# projet_pcb_etu_PIC18.net
KiCad netlist of a schematic drawn in Altium Designer
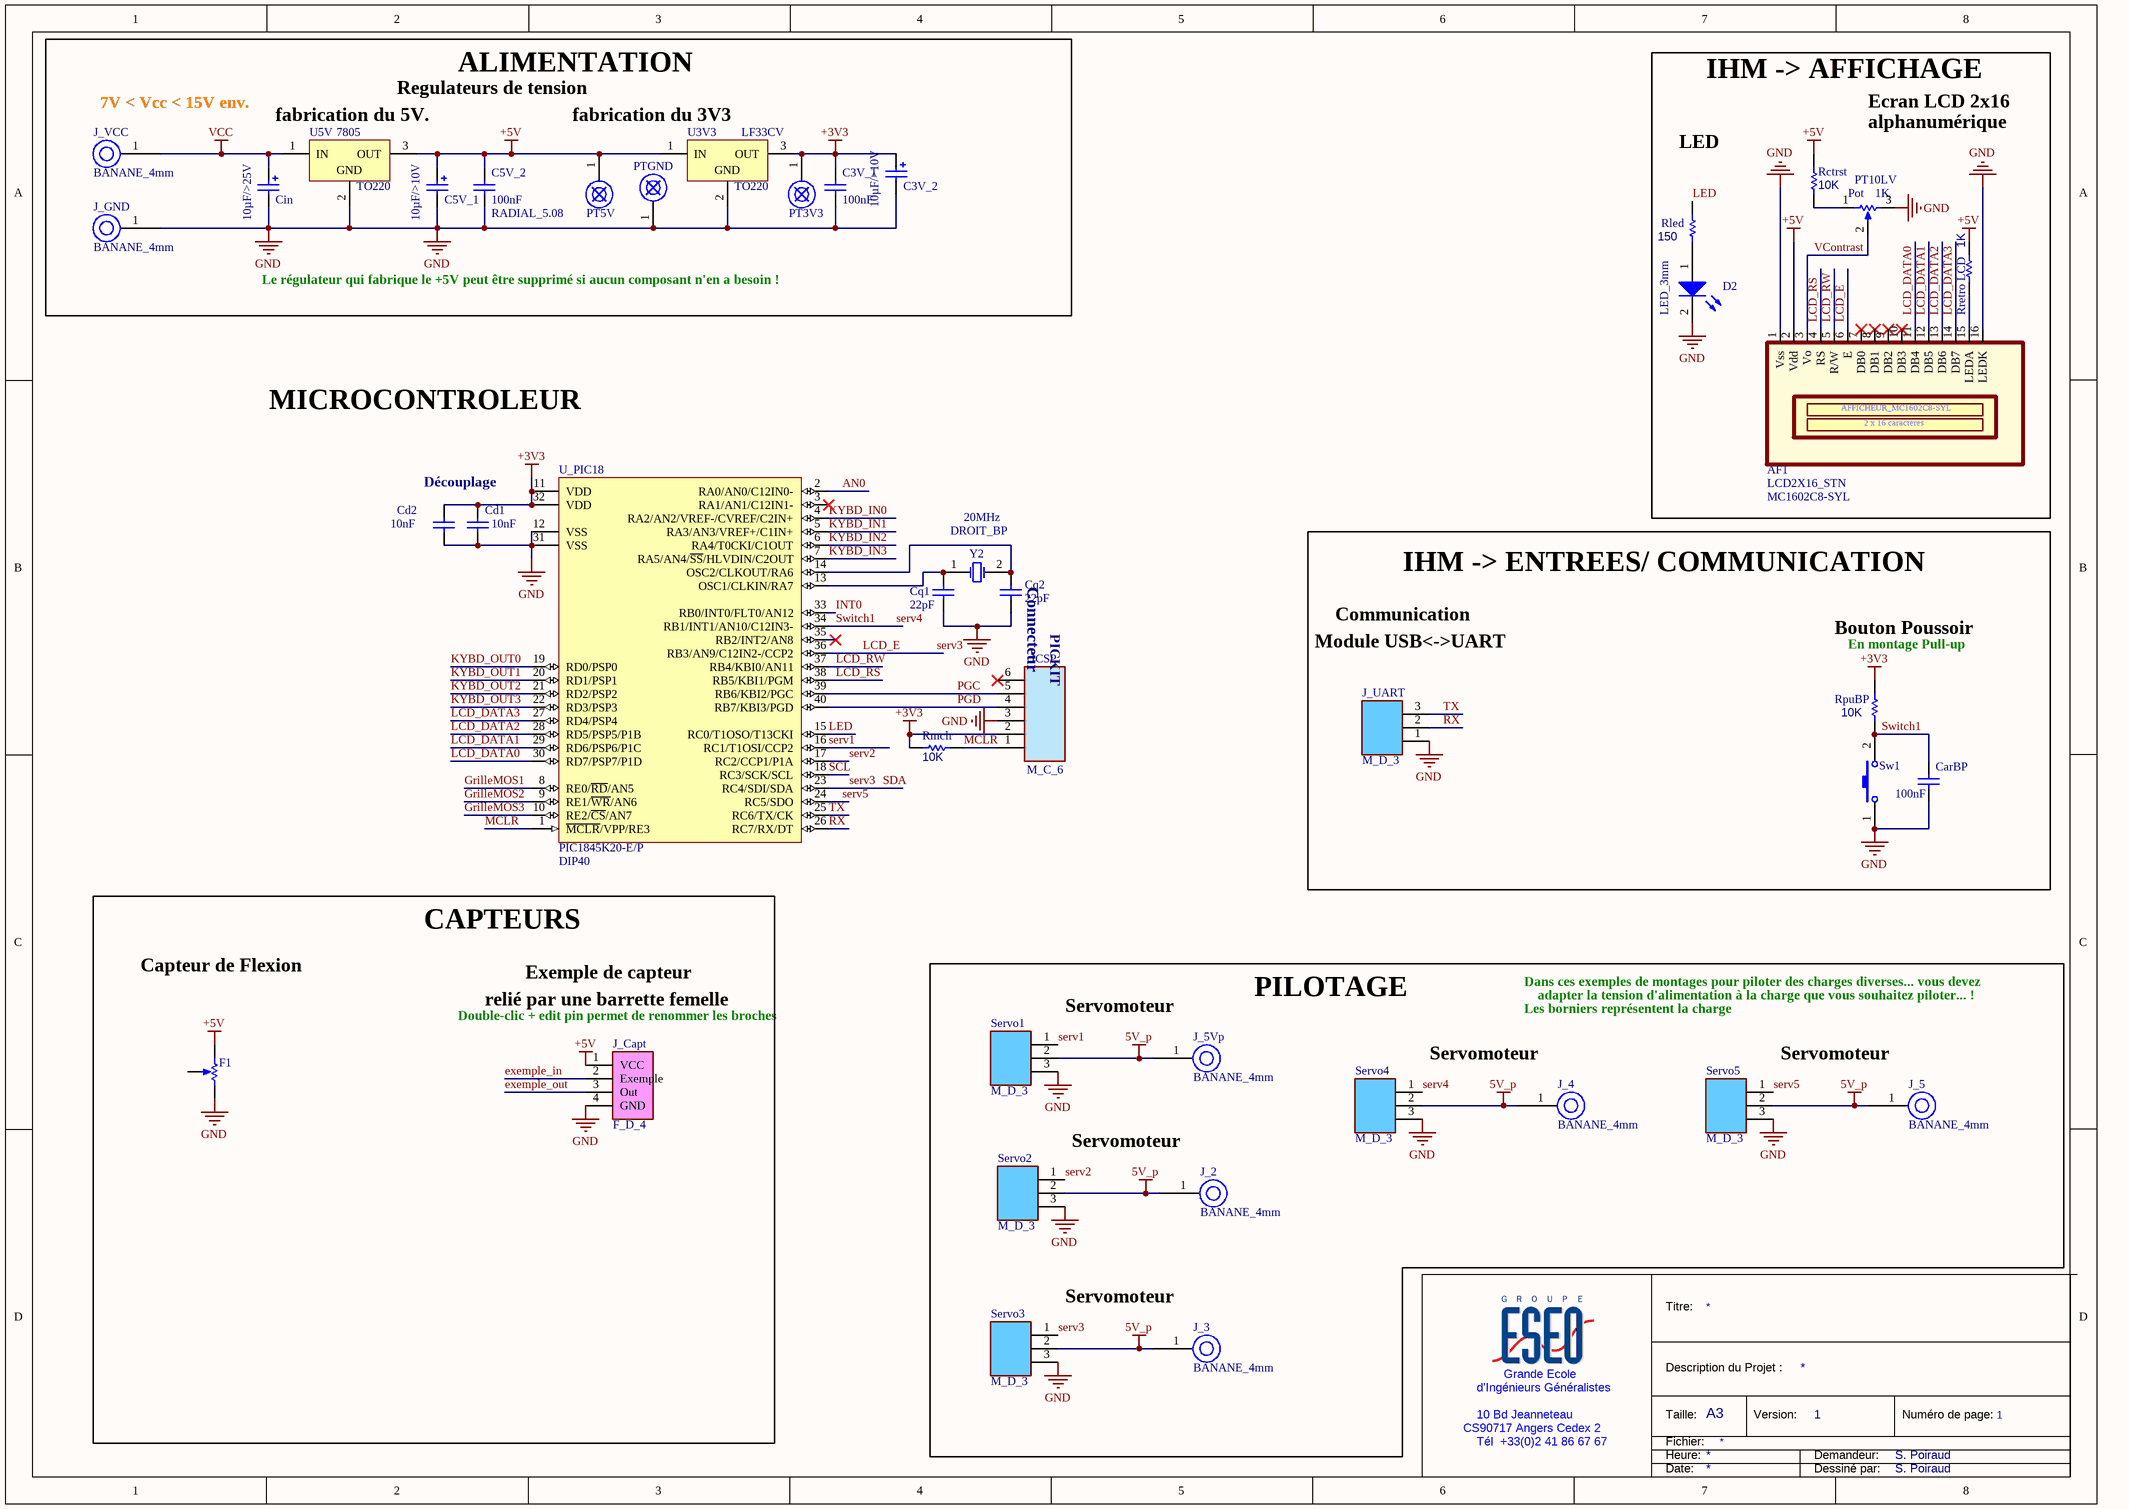
[diagram p0: projet_pcb_etu_PIC18.SchDoc]

(export (version "E")
  (design (tool "Eeschema 10.0.6"))
  (components
    (comp (ref "AF1")
      (value "AFFICHEUR_LCD_2X16_")
      (footprint "AFFICHEUR_LCD_MC1602C8-SYL")
      (description "AFFICHEUR LCD - 2x16 LIGNES - 5X7 DOTS - STN - 80mm x 36mm")
      (fields (field (name "TYPE") "LCD2X16_STN") (field (name "NAME") "MC1602C8-SYL"))
      (libsource (lib "affichage") (part "AFFICHEUR_LCD_MC1602C8-SYL"))
    )
    (comp (ref "C3V_1")
      (value "100nF")
      (footprint "CONDENSATEUR_CERAMIQUE_RADIAL_5.08")
      (description "CONDENSATEUR TRAVERSANT CERAMIQUE RADIAL 5.08mm")
      (fields (field (name "Comment") "CONDENSATEUR_CER_RAD_5.08"))
      (libsource (lib "composants passifs") (part "CONDENSATEUR_CER_RAD_5.08"))
    )
    (comp (ref "C3V_2")
      (value "10µF/>10V")
      (footprint "CONDENSATEUR_POLARISE_ELECTROLYTIQUE_RADIAL_2.0/5.08")
      (description "CONDENSATEUR POLARISE ELECTROLYTIQUE RADIAL 2.0/5.08")
      (fields (field (name "Comment") "CONDENSATEUR_POL_ELECTROLY_RAD_2.0/5.08"))
      (libsource (lib "composants passifs") (part "CONDENSATEUR_POL_ELECTROLY_RAD_2.0/5.08"))
    )
    (comp (ref "C5V_1")
      (value "10µF/>10V")
      (footprint "CONDENSATEUR_POLARISE_ELECTROLYTIQUE_RADIAL_2.0/5.08")
      (description "CONDENSATEUR POLARISE ELECTROLYTIQUE RADIAL 2.0/5.08")
      (fields (field (name "Comment") "CONDENSATEUR_POL_ELECTROLY_RAD_2.0/5.08"))
      (libsource (lib "composants passifs") (part "CONDENSATEUR_POL_ELECTROLY_RAD_2.0/5.08"))
    )
    (comp (ref "C5V_2")
      (value "100nF")
      (footprint "CONDENSATEUR_CERAMIQUE_RADIAL_5.08")
      (description "CONDENSATEUR TRAVERSANT CERAMIQUE RADIAL 5.08mm")
      (fields (field (name "TYPE") "RADIAL_5.08") (field (name "Comment") "CONDENSATEUR_CER_RAD_5.08"))
      (libsource (lib "composants passifs") (part "CONDENSATEUR_CER_RAD_5.08"))
    )
    (comp (ref "CarBP")
      (value "100nF")
      (footprint "CONDENSATEUR_CERAMIQUE_RADIAL_5.08")
      (description "CONDENSATEUR TRAVERSANT CERAMIQUE RADIAL 5.08mm")
      (fields (field (name "Comment") "CONDENSATEUR_CER_RAD_5.08"))
      (libsource (lib "composants passifs") (part "CONDENSATEUR_CER_RAD_5.08"))
    )
    (comp (ref "Cd1")
      (value "10nF")
      (footprint "CONDENSATEUR_CERAMIQUE_RADIAL_5.08")
      (description "CONDENSATEUR TRAVERSANT CERAMIQUE RADIAL 5.08mm")
      (fields (field (name "Comment") "CONDENSATEUR_CER_RAD_5.08"))
      (libsource (lib "composants passifs") (part "CONDENSATEUR_CER_RAD_5.08"))
    )
    (comp (ref "Cd2")
      (value "10nF")
      (footprint "CONDENSATEUR_CERAMIQUE_RADIAL_5.08")
      (description "CONDENSATEUR TRAVERSANT CERAMIQUE RADIAL 5.08mm")
      (fields (field (name "Comment") "CONDENSATEUR_CER_RAD_5.08"))
      (libsource (lib "composants passifs") (part "CONDENSATEUR_CER_RAD_5.08"))
    )
    (comp (ref "Cin")
      (value "10µF/>25V")
      (footprint "CONDENSATEUR_POLARISE_ELECTROLYTIQUE_RADIAL_2.0/5.08")
      (description "CONDENSATEUR POLARISE ELECTROLYTIQUE RADIAL 2.0/5.08")
      (fields (field (name "Comment") "CONDENSATEUR_POL_ELECTROLY_RAD_2.0/5.08"))
      (libsource (lib "composants passifs") (part "CONDENSATEUR_POL_ELECTROLY_RAD_2.0/5.08"))
    )
    (comp (ref "Cq1")
      (value "22pF")
      (footprint "CONDENSATEUR_CERAMIQUE_RADIAL_5.08")
      (description "CONDENSATEUR TRAVERSANT CERAMIQUE RADIAL 5.08mm")
      (fields (field (name "Comment") "CONDENSATEUR_CER_RAD_5.08"))
      (libsource (lib "composants passifs") (part "CONDENSATEUR_CER_RAD_5.08"))
    )
    (comp (ref "Cq2")
      (value "22pF")
      (footprint "CONDENSATEUR_CERAMIQUE_RADIAL_5.08")
      (description "CONDENSATEUR TRAVERSANT CERAMIQUE RADIAL 5.08mm")
      (fields (field (name "Comment") "CONDENSATEUR_CER_RAD_5.08"))
      (libsource (lib "composants passifs") (part "CONDENSATEUR_CER_RAD_5.08"))
    )
    (comp (ref "D2")
      (value "LED_3MM")
      (footprint "LED_3MM")
      (description "LED 3MM - ROUGE/VERTE/JAUNE")
      (fields (field (name "TYPE") "LED_3mm"))
      (libsource (lib "affichage") (part "LED_3MM"))
    )
    (comp (ref "F1")
      (value "Potentiometer")
      (libsource (lib "Simulation Generic Components") (part "Potentiometer"))
    )
    (comp (ref "ICSP")
      (value "BARRETTE_6 CONTACTS_1 RANGEE_MALE_COUDEE")
      (footprint "BARRETTE_6_M_C")
      (description "BARRETTE 6 CONTACTS 1 RANGEE MALE COUDEE")
      (fields (field (name "TYPE") "M_C_6"))
      (libsource (lib "connecteurs") (part "BARRETTE_6 CONTACTS_1 RANGEE_MALE_COUDEE"))
    )
    (comp (ref "J_2")
      (value "DOUILLE BANANE 4mm")
      (footprint "DOUILLE_BANANE_4mm")
      (description "DOUILLE BANANE 4 mm")
      (fields (field (name "TYPE") "BANANE_4mm"))
      (libsource (lib "connecteurs") (part "DOUILLE_BANANE_4mm"))
    )
    (comp (ref "J_3")
      (value "DOUILLE BANANE 4mm")
      (footprint "DOUILLE_BANANE_4mm")
      (description "DOUILLE BANANE 4 mm")
      (fields (field (name "TYPE") "BANANE_4mm"))
      (libsource (lib "connecteurs") (part "DOUILLE_BANANE_4mm"))
    )
    (comp (ref "J_4")
      (value "DOUILLE BANANE 4mm")
      (footprint "DOUILLE_BANANE_4mm")
      (description "DOUILLE BANANE 4 mm")
      (fields (field (name "TYPE") "BANANE_4mm"))
      (libsource (lib "connecteurs") (part "DOUILLE_BANANE_4mm"))
    )
    (comp (ref "J_5")
      (value "DOUILLE BANANE 4mm")
      (footprint "DOUILLE_BANANE_4mm")
      (description "DOUILLE BANANE 4 mm")
      (fields (field (name "TYPE") "BANANE_4mm"))
      (libsource (lib "connecteurs") (part "DOUILLE_BANANE_4mm"))
    )
    (comp (ref "J_5Vp")
      (value "DOUILLE BANANE 4mm")
      (footprint "DOUILLE_BANANE_4mm")
      (description "DOUILLE BANANE 4 mm")
      (fields (field (name "TYPE") "BANANE_4mm"))
      (libsource (lib "connecteurs") (part "DOUILLE_BANANE_4mm"))
    )
    (comp (ref "J_Capt")
      (value "BARRETTE_4 CONTACTS_1 RANGEE_FEMELLE_DROITE")
      (footprint "BARRETTE_4_F_D")
      (description "BARRETTE 4 CONTACTS 1 RANGEE FEMELLE DROITE")
      (fields (field (name "TYPE") "F_D_4"))
      (libsource (lib "connecteurs") (part "BARRETTE_4 CONTACTS_1 RANGEE_FEMELLE_DROITE"))
    )
    (comp (ref "J_GND")
      (value "DOUILLE BANANE 4mm")
      (footprint "DOUILLE_BANANE_4mm")
      (description "DOUILLE BANANE 4 mm")
      (fields (field (name "TYPE") "BANANE_4mm"))
      (libsource (lib "connecteurs") (part "DOUILLE_BANANE_4mm"))
    )
    (comp (ref "J_UART")
      (value "BARRETTE 3 CONTACTS 1 RANGEE MALE DROITE")
      (footprint "BARRETTE_3_M_D")
      (fields (field (name "TYPE") "M_D_3"))
      (libsource (lib "") (part "BARRETTE_3 CONTACTS_1 RANGEE_MALE_DROITE_1"))
    )
    (comp (ref "J_VCC")
      (value "DOUILLE BANANE 4mm")
      (footprint "DOUILLE_BANANE_4mm")
      (description "DOUILLE BANANE 4 mm")
      (fields (field (name "TYPE") "BANANE_4mm"))
      (libsource (lib "connecteurs") (part "DOUILLE_BANANE_4mm"))
    )
    (comp (ref "Pot")
      (value "1K")
      (footprint "TRIMMER_MONOTOUR_PT10LV")
      (description "RESISTANCE VARIABLE_TRAVERSANTE : PT10LV")
      (fields
        (field (name "TYPE") "PT10LV")
        (field (name "Comment") "RESISTANCE_VARIABLE_TRAVERSANTE : PT10LV")
      )
      (libsource (lib "composants passifs") (part "RESISTANCE_VARIABLE_TRAVERSANTE {colon} PT10LV"))
    )
    (comp (ref "PT3V3")
      (value "POINT_TEST")
      (footprint "POINT_TEST")
      (description "POINT TEST")
      (libsource (lib "connecteurs") (part "POINT_TEST"))
    )
    (comp (ref "PT5V")
      (value "POINT_TEST")
      (footprint "POINT_TEST")
      (description "POINT TEST")
      (libsource (lib "connecteurs") (part "POINT_TEST"))
    )
    (comp (ref "PTGND")
      (value "POINT_TEST")
      (footprint "POINT_TEST")
      (description "POINT TEST")
      (libsource (lib "connecteurs") (part "POINT_TEST"))
    )
    (comp (ref "Rctrst")
      (value "10K")
      (footprint "RESISTANCE_1/4W")
      (description "RESISTANCE TRAVERSANTE AXIALE 1/4W")
      (fields (field (name "Comment") "RESISTANCE_AXIALE_1/4W"))
      (libsource (lib "composants passifs") (part "RESISTANCE_AXIALE_1/4W"))
    )
    (comp (ref "Rled")
      (value "150")
      (footprint "RESISTANCE_1/4W")
      (description "RESISTANCE TRAVERSANTE AXIALE 1/4W")
      (fields (field (name "Comment") "RESISTANCE_AXIALE_1/4W"))
      (libsource (lib "composants passifs") (part "RESISTANCE_AXIALE_1/4W"))
    )
    (comp (ref "Rmclr")
      (value "10K")
      (footprint "RESISTANCE_1/4W")
      (description "RESISTANCE TRAVERSANTE AXIALE 1/4W")
      (fields (field (name "Comment") "RESISTANCE_AXIALE_1/4W"))
      (libsource (lib "composants passifs") (part "RESISTANCE_AXIALE_1/4W"))
    )
    (comp (ref "RpuBP")
      (value "10K")
      (footprint "RESISTANCE_1/4W")
      (description "RESISTANCE TRAVERSANTE AXIALE 1/4W")
      (fields (field (name "Comment") "RESISTANCE_AXIALE_1/4W"))
      (libsource (lib "composants passifs") (part "RESISTANCE_AXIALE_1/4W"))
    )
    (comp (ref "Rretro LCD")
      (value "1K")
      (footprint "RESISTANCE_1/4W")
      (description "RESISTANCE TRAVERSANTE AXIALE 1/4W")
      (fields (field (name "Comment") "RESISTANCE_AXIALE_1/4W"))
      (libsource (lib "composants passifs") (part "RESISTANCE_AXIALE_1/4W"))
    )
    (comp (ref "Servo1")
      (value "BARRETTE 3 CONTACTS 1 RANGEE MALE DROITE")
      (footprint "BARRETTE_3_M_D")
      (fields (field (name "TYPE") "M_D_3"))
      (libsource (lib "connecteurs") (part "BARRETTE_3 CONTACTS_1 RANGEE_MALE_DROITE"))
    )
    (comp (ref "Servo2")
      (value "BARRETTE 3 CONTACTS 1 RANGEE MALE DROITE")
      (footprint "BARRETTE_3_M_D")
      (fields (field (name "TYPE") "M_D_3"))
      (libsource (lib "connecteurs") (part "BARRETTE_3 CONTACTS_1 RANGEE_MALE_DROITE"))
    )
    (comp (ref "Servo3")
      (value "BARRETTE 3 CONTACTS 1 RANGEE MALE DROITE")
      (footprint "BARRETTE_3_M_D")
      (fields (field (name "TYPE") "M_D_3"))
      (libsource (lib "connecteurs") (part "BARRETTE_3 CONTACTS_1 RANGEE_MALE_DROITE"))
    )
    (comp (ref "Servo4")
      (value "BARRETTE 3 CONTACTS 1 RANGEE MALE DROITE")
      (footprint "BARRETTE_3_M_D")
      (fields (field (name "TYPE") "M_D_3"))
      (libsource (lib "connecteurs") (part "BARRETTE_3 CONTACTS_1 RANGEE_MALE_DROITE"))
    )
    (comp (ref "Servo5")
      (value "BARRETTE 3 CONTACTS 1 RANGEE MALE DROITE")
      (footprint "BARRETTE_3_M_D")
      (fields (field (name "TYPE") "M_D_3"))
      (libsource (lib "connecteurs") (part "BARRETTE_3 CONTACTS_1 RANGEE_MALE_DROITE"))
    )
    (comp (ref "Sw1")
      (value "BOUTON_POUSSOIR_MINIATURE_TRAVERSANT")
      (footprint "BOUTON_POUSSE_PLAT_6x6")
      (description "BOUTON POUSSOIR MINIATURE TRAVERSANT ON/OFF")
      (libsource (lib "commutation") (part "BOUTON_POUSSOIR_MINIATURE_TRAVERSANT"))
    )
    (comp (ref "U3V3")
      (value "REGULATEUR_TO220_78XX")
      (footprint "REGULATEUR_TO220_78XX")
      (description "REGULATEUR DE TENSION POSITIVE 78XX BOITIER TO220")
      (fields (field (name "TYPE") "LF33CV") (field (name "PACKAGE") "TO220"))
      (libsource (lib "composants actifs") (part "REGULATEUR_TO220_78XX"))
    )
    (comp (ref "U5V")
      (value "REGULATEUR_TO220_78XX")
      (footprint "REGULATEUR_TO220_78XX")
      (description "REGULATEUR DE TENSION POSITIVE 78XX BOITIER TO220")
      (fields (field (name "TYPE") "7805") (field (name "PACKAGE") "TO220"))
      (libsource (lib "composants actifs") (part "REGULATEUR_TO220_78XX"))
    )
    (comp (ref "U_PIC18")
      (value "PIC18F45K20-E/P_DIP40")
      (footprint "DIP40_PAS=2.54_LARG=15.24_LONG=52.5")
      (fields (field (name "TYPE") "PIC1845K20-E/P") (field (name "PACKAGE") "DIP40"))
      (libsource (lib "circuits integres") (part "PIC18F45K20-E/P_DIP40"))
    )
    (comp (ref "Y2")
      (value "20MHz")
      (footprint "QUARTZ_DROIT_BP")
      (description "QUARTZ DROIT BAS PROFIL")
      (fields (field (name "TYPE") "DROIT_BP") (field (name "Comment") "QUARTZ_DROIT_BAS_PROFIL"))
      (libsource (lib "composants passifs") (part "QUARTZ_DROIT_BAS_PROFIL"))
    )
  )
  (nets
    (net (code "1") (name "+3V3") (class "Default")
      (node (ref "C3V_1") (pin "2") (pinfunction "2_2") (pintype "passive"))
      (node (ref "C3V_2") (pin "1") (pinfunction "1_1") (pintype "passive"))
      (node (ref "Cd1") (pin "2") (pinfunction "2_2") (pintype "passive"))
      (node (ref "Cd2") (pin "2") (pinfunction "2_2") (pintype "passive"))
      (node (ref "ICSP") (pin "2") (pinfunction "2_2") (pintype "passive"))
      (node (ref "PT3V3") (pin "1") (pinfunction "3_1") (pintype "passive"))
      (node (ref "Rmclr") (pin "2") (pinfunction "2_2") (pintype "passive"))
      (node (ref "RpuBP") (pin "1") (pinfunction "1_1") (pintype "passive"))
      (node (ref "U3V3") (pin "3") (pinfunction "OUT_3") (pintype "power_in"))
      (node (ref "U_PIC18") (pin "11") (pinfunction "VDD_11") (pintype "power_in"))
      (node (ref "U_PIC18") (pin "32") (pinfunction "VDD_32") (pintype "power_in"))
    )
    (net (code "2") (name "+5V") (class "Default")
      (node (ref "AF1") (pin "2") (pinfunction "Vdd_2") (pintype "passive"))
      (node (ref "C5V_1") (pin "1") (pinfunction "1_1") (pintype "passive"))
      (node (ref "C5V_2") (pin "2") (pinfunction "2_2") (pintype "passive"))
      (node (ref "F1") (pin "1") (pinfunction "TOP_1") (pintype "passive"))
      (node (ref "J_Capt") (pin "1") (pinfunction "VCC_1") (pintype "passive"))
      (node (ref "PT5V") (pin "1") (pinfunction "3_1") (pintype "passive"))
      (node (ref "Rctrst") (pin "1") (pinfunction "1_1") (pintype "passive"))
      (node (ref "Rretro LCD") (pin "1") (pinfunction "1_1") (pintype "passive"))
      (node (ref "U3V3") (pin "1") (pinfunction "IN_1") (pintype "power_in"))
      (node (ref "U5V") (pin "3") (pinfunction "OUT_3") (pintype "power_in"))
    )
    (net (code "3") (name "/AN0") (class "Default")
      (node (ref "U_PIC18") (pin "2") (pinfunction "RA0/AN0/C12IN0-_2") (pintype "bidirectional"))
    )
    (net (code "4") (name "/GrilleMOS1") (class "Default")
      (node (ref "U_PIC18") (pin "8") (pinfunction "RE0/~{RD}/AN5_8") (pintype "bidirectional"))
    )
    (net (code "5") (name "/GrilleMOS2") (class "Default")
      (node (ref "U_PIC18") (pin "9") (pinfunction "RE1/~{WR}/AN6_9") (pintype "bidirectional"))
    )
    (net (code "6") (name "/GrilleMOS3") (class "Default")
      (node (ref "U_PIC18") (pin "10") (pinfunction "RE2/~{CS}/AN7_10") (pintype "bidirectional"))
    )
    (net (code "7") (name "/INT0") (class "Default")
      (node (ref "U_PIC18") (pin "33") (pinfunction "RB0/INT0/FLT0/AN12_33") (pintype "bidirectional"))
    )
    (net (code "8") (name "/KYBD_IN0") (class "Default")
      (node (ref "U_PIC18") (pin "4") (pinfunction "RA2/AN2/VREF-/CVREF/C2IN+_4") (pintype "bidirectional"))
    )
    (net (code "9") (name "/KYBD_IN1") (class "Default")
      (node (ref "U_PIC18") (pin "5") (pinfunction "RA3/AN3/VREF+/C1IN+_5") (pintype "bidirectional"))
    )
    (net (code "10") (name "/KYBD_IN2") (class "Default")
      (node (ref "U_PIC18") (pin "6") (pinfunction "RA4/T0CKI/C1OUT_6") (pintype "bidirectional"))
    )
    (net (code "11") (name "/KYBD_IN3") (class "Default")
      (node (ref "U_PIC18") (pin "7") (pinfunction "RA5/AN4/~{SS}/HLVDIN/C2OUT_7") (pintype "bidirectional"))
    )
    (net (code "12") (name "/KYBD_OUT0") (class "Default")
      (node (ref "U_PIC18") (pin "19") (pinfunction "RD0/PSP0_19") (pintype "bidirectional"))
    )
    (net (code "13") (name "/KYBD_OUT1") (class "Default")
      (node (ref "U_PIC18") (pin "20") (pinfunction "RD1/PSP1_20") (pintype "bidirectional"))
    )
    (net (code "14") (name "/KYBD_OUT2") (class "Default")
      (node (ref "U_PIC18") (pin "21") (pinfunction "RD2/PSP2_21") (pintype "bidirectional"))
    )
    (net (code "15") (name "/KYBD_OUT3") (class "Default")
      (node (ref "U_PIC18") (pin "22") (pinfunction "RD3/PSP3_22") (pintype "bidirectional"))
    )
    (net (code "16") (name "/LCD_DATA0") (class "Default")
      (node (ref "AF1") (pin "11") (pinfunction "DB4_11") (pintype "passive"))
      (node (ref "U_PIC18") (pin "30") (pinfunction "RD7/PSP7/P1D_30") (pintype "bidirectional"))
    )
    (net (code "17") (name "/LCD_DATA1") (class "Default")
      (node (ref "AF1") (pin "12") (pinfunction "DB5_12") (pintype "passive"))
      (node (ref "U_PIC18") (pin "29") (pinfunction "RD6/PSP6/P1C_29") (pintype "bidirectional"))
    )
    (net (code "18") (name "/LCD_DATA2") (class "Default")
      (node (ref "AF1") (pin "13") (pinfunction "DB6_13") (pintype "passive"))
      (node (ref "U_PIC18") (pin "28") (pinfunction "RD5/PSP5/P1B_28") (pintype "bidirectional"))
    )
    (net (code "19") (name "/LCD_DATA3") (class "Default")
      (node (ref "AF1") (pin "14") (pinfunction "DB7_14") (pintype "passive"))
      (node (ref "U_PIC18") (pin "27") (pinfunction "RD4/PSP4_27") (pintype "bidirectional"))
    )
    (net (code "20") (name "/LCD_E") (class "Default")
      (node (ref "AF1") (pin "6") (pinfunction "E_6") (pintype "passive"))
      (node (ref "Servo3") (pin "1") (pinfunction "1_1") (pintype "passive"))
      (node (ref "U_PIC18") (pin "23") (pinfunction "RC4/SDI/SDA_23") (pintype "bidirectional"))
      (node (ref "U_PIC18") (pin "36") (pinfunction "RB3/AN9/C12IN2-/CCP2_36") (pintype "bidirectional"))
    )
    (net (code "21") (name "/LCD_RS") (class "Default")
      (node (ref "AF1") (pin "4") (pinfunction "RS_4") (pintype "passive"))
      (node (ref "U_PIC18") (pin "38") (pinfunction "RB5/KBI1/PGM_38") (pintype "bidirectional"))
    )
    (net (code "22") (name "/LCD_RW") (class "Default")
      (node (ref "AF1") (pin "5") (pinfunction "R/W_5") (pintype "passive"))
      (node (ref "U_PIC18") (pin "37") (pinfunction "RB4/KBI0/AN11_37") (pintype "bidirectional"))
    )
    (net (code "23") (name "/LED") (class "Default")
      (node (ref "Rled") (pin "1") (pinfunction "1_1") (pintype "passive"))
      (node (ref "U_PIC18") (pin "15") (pinfunction "RC0/T1OSO/T13CKI_15") (pintype "bidirectional"))
    )
    (net (code "24") (name "/MCLR") (class "Default")
      (node (ref "ICSP") (pin "1") (pinfunction "1_1") (pintype "passive"))
      (node (ref "Rmclr") (pin "1") (pinfunction "1_1") (pintype "passive"))
      (node (ref "U_PIC18") (pin "1") (pinfunction "~{MCLR}/VPP/RE3_1") (pintype "input"))
    )
    (net (code "25") (name "/PGC") (class "Default")
      (node (ref "ICSP") (pin "5") (pinfunction "5_5") (pintype "passive"))
      (node (ref "U_PIC18") (pin "39") (pinfunction "RB6/KBI2/PGC_39") (pintype "bidirectional"))
    )
    (net (code "26") (name "/PGD") (class "Default")
      (node (ref "ICSP") (pin "4") (pinfunction "4_4") (pintype "passive"))
      (node (ref "U_PIC18") (pin "40") (pinfunction "RB7/KBI3/PGD_40") (pintype "bidirectional"))
    )
    (net (code "27") (name "/RX") (class "Default")
      (node (ref "J_UART") (pin "2") (pinfunction "2_2") (pintype "passive"))
      (node (ref "U_PIC18") (pin "26") (pinfunction "RC7/RX/DT_26") (pintype "bidirectional"))
    )
    (net (code "28") (name "/SCL") (class "Default")
      (node (ref "U_PIC18") (pin "18") (pinfunction "RC3/SCK/SCL_18") (pintype "bidirectional"))
    )
    (net (code "29") (name "/Switch1") (class "Default")
      (node (ref "CarBP") (pin "2") (pinfunction "2_2") (pintype "passive"))
      (node (ref "RpuBP") (pin "2") (pinfunction "2_2") (pintype "passive"))
      (node (ref "Servo4") (pin "1") (pinfunction "1_1") (pintype "passive"))
      (node (ref "Sw1") (pin "2") (pinfunction "2_2") (pintype "passive"))
      (node (ref "U_PIC18") (pin "34") (pinfunction "RB1/INT1/AN10/C12IN3-_34") (pintype "bidirectional"))
    )
    (net (code "30") (name "/TX") (class "Default")
      (node (ref "J_UART") (pin "3") (pinfunction "3_3") (pintype "passive"))
      (node (ref "U_PIC18") (pin "25") (pinfunction "RC6/TX/CK_25") (pintype "bidirectional"))
    )
    (net (code "31") (name "/VContrast") (class "Default")
      (node (ref "AF1") (pin "3") (pinfunction "Vo_3") (pintype "passive"))
      (node (ref "Pot") (pin "2") (pinfunction "2_2") (pintype "passive"))
    )
    (net (code "32") (name "/exemple_in") (class "Default")
      (node (ref "J_Capt") (pin "2") (pinfunction "Exemple_2") (pintype "passive"))
    )
    (net (code "33") (name "/exemple_out") (class "Default")
      (node (ref "J_Capt") (pin "3") (pinfunction "Out_3") (pintype "passive"))
    )
    (net (code "34") (name "/serv1") (class "Default")
      (node (ref "Servo1") (pin "1") (pinfunction "1_1") (pintype "passive"))
      (node (ref "U_PIC18") (pin "16") (pinfunction "RC1/T1OSI/CCP2_16") (pintype "bidirectional"))
    )
    (net (code "35") (name "/serv2") (class "Default")
      (node (ref "Servo2") (pin "1") (pinfunction "1_1") (pintype "passive"))
      (node (ref "U_PIC18") (pin "17") (pinfunction "RC2/CCP1/P1A_17") (pintype "bidirectional"))
    )
    (net (code "36") (name "/serv5") (class "Default")
      (node (ref "Servo5") (pin "1") (pinfunction "1_1") (pintype "passive"))
      (node (ref "U_PIC18") (pin "24") (pinfunction "RC5/SDO_24") (pintype "bidirectional"))
    )
    (net (code "37") (name "5V_p") (class "Default")
      (node (ref "J_2") (pin "1") (pinfunction "1_1") (pintype "passive"))
      (node (ref "J_3") (pin "1") (pinfunction "1_1") (pintype "passive"))
      (node (ref "J_4") (pin "1") (pinfunction "1_1") (pintype "passive"))
      (node (ref "J_5") (pin "1") (pinfunction "1_1") (pintype "passive"))
      (node (ref "J_5Vp") (pin "1") (pinfunction "1_1") (pintype "passive"))
      (node (ref "Servo1") (pin "2") (pinfunction "2_2") (pintype "passive"))
      (node (ref "Servo2") (pin "2") (pinfunction "2_2") (pintype "passive"))
      (node (ref "Servo3") (pin "2") (pinfunction "2_2") (pintype "passive"))
      (node (ref "Servo4") (pin "2") (pinfunction "2_2") (pintype "passive"))
      (node (ref "Servo5") (pin "2") (pinfunction "2_2") (pintype "passive"))
    )
    (net (code "38") (name "GND") (class "Default")
      (node (ref "AF1") (pin "1") (pinfunction "Vss_1") (pintype "passive"))
      (node (ref "AF1") (pin "16") (pinfunction "LEDK_16") (pintype "passive"))
      (node (ref "C3V_1") (pin "1") (pinfunction "1_1") (pintype "passive"))
      (node (ref "C3V_2") (pin "2") (pinfunction "2_2") (pintype "passive"))
      (node (ref "C5V_1") (pin "2") (pinfunction "2_2") (pintype "passive"))
      (node (ref "C5V_2") (pin "1") (pinfunction "1_1") (pintype "passive"))
      (node (ref "CarBP") (pin "1") (pinfunction "1_1") (pintype "passive"))
      (node (ref "Cd1") (pin "1") (pinfunction "1_1") (pintype "passive"))
      (node (ref "Cd2") (pin "1") (pinfunction "1_1") (pintype "passive"))
      (node (ref "Cin") (pin "2") (pinfunction "2_2") (pintype "passive"))
      (node (ref "Cq1") (pin "2") (pinfunction "2_2") (pintype "passive"))
      (node (ref "Cq2") (pin "2") (pinfunction "2_2") (pintype "passive"))
      (node (ref "D2") (pin "2") (pinfunction "2_2") (pintype "passive"))
      (node (ref "F1") (pin "2") (pinfunction "BOT_2") (pintype "passive"))
      (node (ref "ICSP") (pin "3") (pinfunction "3_3") (pintype "passive"))
      (node (ref "J_Capt") (pin "4") (pinfunction "GND_4") (pintype "passive"))
      (node (ref "J_GND") (pin "1") (pinfunction "1_1") (pintype "passive"))
      (node (ref "J_UART") (pin "1") (pinfunction "1_1") (pintype "passive"))
      (node (ref "PTGND") (pin "1") (pinfunction "3_1") (pintype "passive"))
      (node (ref "Pot") (pin "3") (pinfunction "3_3") (pintype "passive"))
      (node (ref "Servo1") (pin "3") (pinfunction "3_3") (pintype "passive"))
      (node (ref "Servo2") (pin "3") (pinfunction "3_3") (pintype "passive"))
      (node (ref "Servo3") (pin "3") (pinfunction "3_3") (pintype "passive"))
      (node (ref "Servo4") (pin "3") (pinfunction "3_3") (pintype "passive"))
      (node (ref "Servo5") (pin "3") (pinfunction "3_3") (pintype "passive"))
      (node (ref "Sw1") (pin "1") (pinfunction "1_1") (pintype "passive"))
      (node (ref "U3V3") (pin "2") (pinfunction "GND_2") (pintype "power_in"))
      (node (ref "U5V") (pin "2") (pinfunction "GND_2") (pintype "power_in"))
      (node (ref "U_PIC18") (pin "12") (pinfunction "VSS_12") (pintype "power_in"))
      (node (ref "U_PIC18") (pin "31") (pinfunction "VSS_31") (pintype "power_in"))
    )
    (net (code "39") (name "Net-(AF1-LEDA)") (class "Default")
      (node (ref "AF1") (pin "15") (pinfunction "LEDA_15") (pintype "passive"))
      (node (ref "Rretro LCD") (pin "2") (pinfunction "2_2") (pintype "passive"))
    )
    (net (code "40") (name "Net-(D2-Pad1)") (class "Default")
      (node (ref "D2") (pin "1") (pinfunction "1_1") (pintype "passive"))
      (node (ref "Rled") (pin "2") (pinfunction "2_2") (pintype "passive"))
    )
    (net (code "41") (name "Net-(Pot-Pad1)") (class "Default")
      (node (ref "Pot") (pin "1") (pinfunction "1_1") (pintype "passive"))
      (node (ref "Rctrst") (pin "2") (pinfunction "2_2") (pintype "passive"))
    )
    (net (code "42") (name "Net-(U_PIC18-OSC1{slash}CLKIN{slash}RA7)") (class "Default")
      (node (ref "Cq1") (pin "1") (pinfunction "1_1") (pintype "passive"))
      (node (ref "U_PIC18") (pin "13") (pinfunction "OSC1/CLKIN/RA7_13") (pintype "bidirectional"))
      (node (ref "Y2") (pin "1") (pinfunction "OSC1_1") (pintype "passive"))
    )
    (net (code "43") (name "Net-(U_PIC18-OSC2{slash}CLKOUT{slash}RA6)") (class "Default")
      (node (ref "Cq2") (pin "1") (pinfunction "1_1") (pintype "passive"))
      (node (ref "U_PIC18") (pin "14") (pinfunction "OSC2/CLKOUT/RA6_14") (pintype "bidirectional"))
      (node (ref "Y2") (pin "2") (pinfunction "OSC2_2") (pintype "passive"))
    )
    (net (code "44") (name "VCC") (class "Default")
      (node (ref "Cin") (pin "1") (pinfunction "1_1") (pintype "passive"))
      (node (ref "J_VCC") (pin "1") (pinfunction "1_1") (pintype "passive"))
      (node (ref "U5V") (pin "1") (pinfunction "IN_1") (pintype "power_in"))
    )
    (net (code "45") (name "unconnected-(AF1-DB0-Pad7)") (class "Default")
      (node (ref "AF1") (pin "7") (pinfunction "DB0_7") (pintype "passive+no_connect"))
    )
    (net (code "46") (name "unconnected-(AF1-DB1-Pad8)") (class "Default")
      (node (ref "AF1") (pin "8") (pinfunction "DB1_8") (pintype "passive+no_connect"))
    )
    (net (code "47") (name "unconnected-(AF1-DB2-Pad9)") (class "Default")
      (node (ref "AF1") (pin "9") (pinfunction "DB2_9") (pintype "passive+no_connect"))
    )
    (net (code "48") (name "unconnected-(AF1-DB3-Pad10)") (class "Default")
      (node (ref "AF1") (pin "10") (pinfunction "DB3_10") (pintype "passive+no_connect"))
    )
    (net (code "49") (name "unconnected-(F1-TAP-Pad3)") (class "Default")
      (node (ref "F1") (pin "3") (pinfunction "TAP_3") (pintype "passive"))
    )
    (net (code "50") (name "unconnected-(ICSP-Pad6)") (class "Default")
      (node (ref "ICSP") (pin "6") (pinfunction "6_6") (pintype "passive+no_connect"))
    )
    (net (code "51") (name "unconnected-(U_PIC18-RA1{slash}AN1{slash}C12IN1--Pad3)") (class "Default")
      (node (ref "U_PIC18") (pin "3") (pinfunction "RA1/AN1/C12IN1-_3") (pintype "bidirectional+no_connect"))
    )
    (net (code "52") (name "unconnected-(U_PIC18-RB2{slash}INT2{slash}AN8-Pad35)") (class "Default")
      (node (ref "U_PIC18") (pin "35") (pinfunction "RB2/INT2/AN8_35") (pintype "bidirectional+no_connect"))
    )
  )
)
